# LPCOExtended.net
KiCad netlist of a schematic drawn in Altium Designer
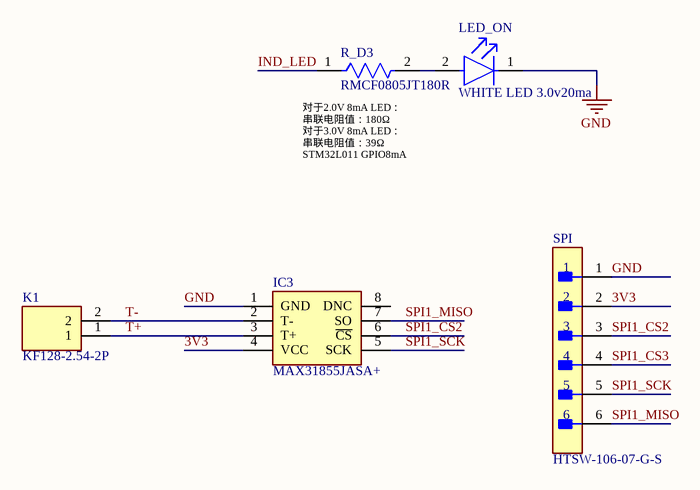
[diagram p0: LPCOExtended.SchDoc]

(export (version "E")
  (design (tool "Eeschema 10.0.6"))
  (components
    (comp (ref "IC3")
      (value "MAX31855JASA+")
      (footprint "SamacSys:SOIC127P600X175-8N")
      (description "Integrated Circuit")
      (fields (field (name "MOUSER PART NUMBER") "700-MAX31855JASA+"))
      (libsource (lib "*") (part "MAX31855JASA+"))
    )
    (comp (ref "K1")
      (value "KF128-2.54-2P")
      (footprint "SamacSys:KF1282542P")
      (description "Connector")
      (libsource (lib "*") (part "KF128-2.54-2P"))
    )
    (comp (ref "LED_ON")
      (value "WHITE LED 3.0v20ma")
      (footprint "FP-SML-LX0805UWC-TR-MFG")
      (description "SML-LX0805UWC-TR White LED, 0805 Diffused, Rectangle Lens SMD package")
      (libsource (lib "Altium Content Vault") (part "8706943c75ba83719d021d2fdc84c58"))
    )
    (comp (ref "R_D3")
      (value "RMCF0805JT180R")
      (footprint "FP-RMCF0805-IPC_B")
      (description "180Ω ±5% 0.125W 0805 Thick Film Chip Resistor AEC-Q200 compliant")
      (fields (field (name "TOLERANCE") "5%"))
      (libsource (lib "Altium Content Vault") (part "1029c3af85768c4190bb7ad29bc67b5"))
    )
    (comp (ref "SPI")
      (value "HTSW-106-07-G-S")
      (footprint "FP-HTSW-106-07-G-S-MFG")
      (description "CONN HEADER VERT 6POS 2.54MM")
      (libsource (lib "Altium Content Vault") (part "f2cb566baf1c37ab5a3b8e90bbeafd6"))
    )
  )
  (nets
    (net (code "1") (name "/3V3") (class "Default")
      (node (ref "IC3") (pin "4") (pinfunction "VCC_4") (pintype "passive"))
      (node (ref "SPI") (pin "2") (pinfunction "2_2") (pintype "passive"))
    )
    (net (code "2") (name "/IND_LED") (class "Default")
      (node (ref "R_D3") (pin "1") (pinfunction "1_1") (pintype "passive"))
    )
    (net (code "3") (name "/SPI1_CS2") (class "Default")
      (node (ref "IC3") (pin "6") (pinfunction "~{CS}_6") (pintype "passive"))
      (node (ref "SPI") (pin "3") (pinfunction "3_3") (pintype "passive"))
    )
    (net (code "4") (name "/SPI1_CS3") (class "Default")
      (node (ref "SPI") (pin "4") (pinfunction "4_4") (pintype "passive"))
    )
    (net (code "5") (name "/SPI1_MISO") (class "Default")
      (node (ref "IC3") (pin "7") (pinfunction "SO_7") (pintype "passive"))
      (node (ref "SPI") (pin "6") (pinfunction "6_6") (pintype "passive"))
    )
    (net (code "6") (name "/SPI1_SCK") (class "Default")
      (node (ref "IC3") (pin "5") (pinfunction "SCK_5") (pintype "passive"))
      (node (ref "SPI") (pin "5") (pinfunction "5_5") (pintype "passive"))
    )
    (net (code "7") (name "/T+") (class "Default")
      (node (ref "IC3") (pin "3") (pinfunction "T+_3") (pintype "passive"))
      (node (ref "K1") (pin "1") (pinfunction "1_1") (pintype "passive"))
    )
    (net (code "8") (name "/T-") (class "Default")
      (node (ref "IC3") (pin "2") (pinfunction "T-_2") (pintype "passive"))
      (node (ref "K1") (pin "2") (pinfunction "2_2") (pintype "passive"))
    )
    (net (code "9") (name "GND") (class "Default")
      (node (ref "IC3") (pin "1") (pinfunction "GND_1") (pintype "passive"))
      (node (ref "LED_ON") (pin "1") (pinfunction "C_1") (pintype "passive"))
      (node (ref "SPI") (pin "1") (pinfunction "1_1") (pintype "passive"))
    )
    (net (code "10") (name "Net-(LED_ON-A)") (class "Default")
      (node (ref "LED_ON") (pin "2") (pinfunction "A_2") (pintype "passive"))
      (node (ref "R_D3") (pin "2") (pinfunction "2_2") (pintype "passive"))
    )
    (net (code "11") (name "unconnected-(IC3-DNC-Pad8)") (class "Default")
      (node (ref "IC3") (pin "8") (pinfunction "DNC_8") (pintype "passive"))
    )
  )
)
